# UniRF-Rev01.net
KiCad netlist of a schematic drawn in EAGLE
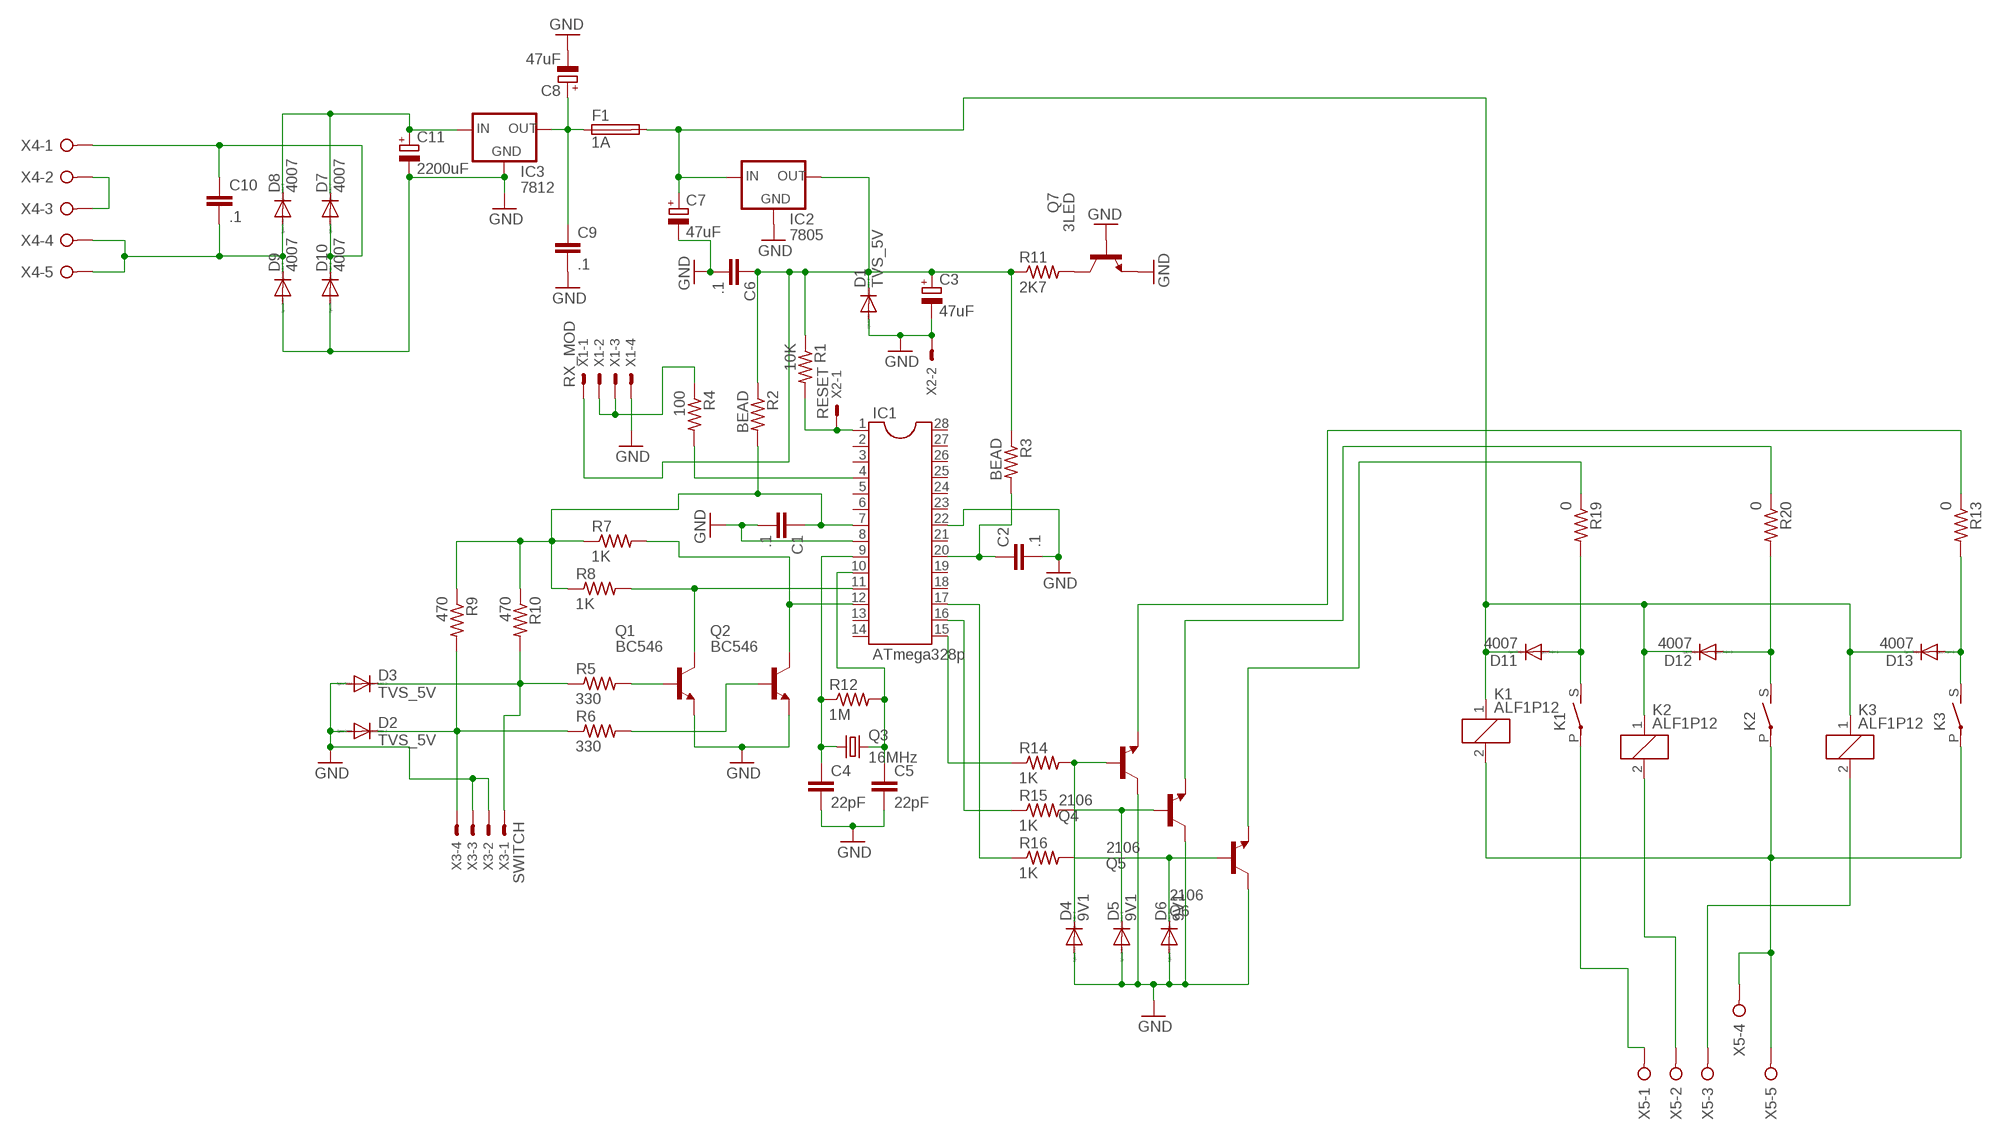
[diagram p0: schematic, sheet 1]

(export (version "E")
  (design (tool "Eeschema 10.0.6"))
  (components
    (comp (ref "C1")
      (value ".1")
      (footprint "eagle-import:C1210K")
      (libsource (lib "eagle-import") (part "C-EUC1210K"))
    )
    (comp (ref "C2")
      (value ".1")
      (footprint "eagle-import:C1210K")
      (libsource (lib "eagle-import") (part "C-EUC1210K"))
    )
    (comp (ref "C3")
      (value "47uF")
      (footprint "eagle-import:E5-8,5")
      (libsource (lib "eagle-import") (part "CPOL-EUE5-8.5"))
    )
    (comp (ref "C4")
      (value "22pF")
      (footprint "eagle-import:C1210K")
      (libsource (lib "eagle-import") (part "C-EUC1210K"))
    )
    (comp (ref "C5")
      (value "22pF")
      (footprint "eagle-import:C1210K")
      (libsource (lib "eagle-import") (part "C-EUC1210K"))
    )
    (comp (ref "C6")
      (value ".1")
      (footprint "eagle-import:C1210K")
      (libsource (lib "eagle-import") (part "C-EUC1210K"))
    )
    (comp (ref "C7")
      (value "47uF")
      (footprint "eagle-import:E5-8,5")
      (libsource (lib "eagle-import") (part "CPOL-EUE5-8.5"))
    )
    (comp (ref "C8")
      (value "47uF")
      (footprint "eagle-import:E5-8,5")
      (libsource (lib "eagle-import") (part "CPOL-EUE5-8.5"))
    )
    (comp (ref "C9")
      (value ".1")
      (footprint "eagle-import:C1210K")
      (libsource (lib "eagle-import") (part "C-EUC1210K"))
    )
    (comp (ref "C10")
      (value ".1")
      (footprint "eagle-import:C075-042X103")
      (libsource (lib "eagle-import") (part "C-EU075-042X103"))
    )
    (comp (ref "C11")
      (value "2200uF")
      (footprint "eagle-import:E7,5-18")
      (libsource (lib "eagle-import") (part "CPOL-EUE7.5-18"))
    )
    (comp (ref "D1")
      (value "TVS_5V")
      (footprint "eagle-import:DO35-10")
      (libsource (lib "eagle-import") (part "1N4148DO35-10"))
    )
    (comp (ref "D2")
      (value "TVS_5V")
      (footprint "eagle-import:DO35-10")
      (libsource (lib "eagle-import") (part "1N4148DO35-10"))
    )
    (comp (ref "D3")
      (value "TVS_5V")
      (footprint "eagle-import:DO35-10")
      (libsource (lib "eagle-import") (part "1N4148DO35-10"))
    )
    (comp (ref "D4")
      (value "9V1")
      (footprint "eagle-import:DO35-7")
      (libsource (lib "eagle-import") (part "1N4148DO35-7"))
    )
    (comp (ref "D5")
      (value "9V1")
      (footprint "eagle-import:DO35-7")
      (libsource (lib "eagle-import") (part "1N4148DO35-7"))
    )
    (comp (ref "D6")
      (value "9V1")
      (footprint "eagle-import:DO35-7")
      (libsource (lib "eagle-import") (part "1N4148DO35-7"))
    )
    (comp (ref "D7")
      (value "4007")
      (footprint "eagle-import:DO204-10")
      (libsource (lib "eagle-import") (part "1N5059"))
    )
    (comp (ref "D8")
      (value "4007")
      (footprint "eagle-import:DO204-10")
      (libsource (lib "eagle-import") (part "1N5059"))
    )
    (comp (ref "D9")
      (value "4007")
      (footprint "eagle-import:DO204-10")
      (libsource (lib "eagle-import") (part "1N5059"))
    )
    (comp (ref "D10")
      (value "4007")
      (footprint "eagle-import:DO204-10")
      (libsource (lib "eagle-import") (part "1N5059"))
    )
    (comp (ref "D11")
      (value "4007")
      (footprint "eagle-import:DO35-10")
      (libsource (lib "eagle-import") (part "1N4148DO35-10"))
    )
    (comp (ref "D12")
      (value "4007")
      (footprint "eagle-import:DO35-10")
      (libsource (lib "eagle-import") (part "1N4148DO35-10"))
    )
    (comp (ref "D13")
      (value "4007")
      (footprint "eagle-import:DO35-10")
      (libsource (lib "eagle-import") (part "1N4148DO35-10"))
    )
    (comp (ref "F1")
      (value "1A")
      (footprint "eagle-import:19560")
      (fields (field (name "MPN") "56000001009"))
      (libsource (lib "eagle-import") (part "19560"))
    )
    (comp (ref "IC1")
      (value "ATmega328p")
      (footprint "eagle-import:DIL28-3")
      (libsource (lib "eagle-import") (part "DIL28-3"))
    )
    (comp (ref "IC2")
      (value "7805")
      (footprint "eagle-import:78XXS")
      (libsource (lib "eagle-import") (part "78XXS"))
    )
    (comp (ref "IC3")
      (value "7812")
      (footprint "eagle-import:78XXS")
      (libsource (lib "eagle-import") (part "78XXS"))
    )
    (comp (ref "K1")
      (value "ALF1P12")
      (footprint "eagle-import:G2RA")
      (libsource (lib "eagle-import") (part "G2RA"))
    )
    (comp (ref "K2")
      (value "ALF1P12")
      (footprint "eagle-import:G2RA")
      (libsource (lib "eagle-import") (part "G2RA"))
    )
    (comp (ref "K3")
      (value "ALF1P12")
      (footprint "eagle-import:G2RA")
      (libsource (lib "eagle-import") (part "G2RA"))
    )
    (comp (ref "Q1")
      (value "BC546")
      (footprint "eagle-import:TO92-EBC")
      (libsource (lib "eagle-import") (part "BC546A"))
    )
    (comp (ref "Q2")
      (value "BC546")
      (footprint "eagle-import:TO92-EBC")
      (libsource (lib "eagle-import") (part "BC546A"))
    )
    (comp (ref "Q3")
      (value "16MHz")
      (footprint "eagle-import:HC49_S")
      (libsource (lib "eagle-import") (part "CRYSTALHC49S"))
    )
    (comp (ref "Q4")
      (value "2106")
      (footprint "eagle-import:TO92-EBC")
      (libsource (lib "eagle-import") (part "BC546A"))
    )
    (comp (ref "Q5")
      (value "2106")
      (footprint "eagle-import:TO92-EBC")
      (libsource (lib "eagle-import") (part "BC546A"))
    )
    (comp (ref "Q6")
      (value "2106")
      (footprint "eagle-import:TO92-EBC")
      (libsource (lib "eagle-import") (part "BC546A"))
    )
    (comp (ref "Q7")
      (value "3LED")
      (footprint "eagle-import:TO92-EBC")
      (libsource (lib "eagle-import") (part "BC546A"))
    )
    (comp (ref "R1")
      (value "10K")
      (footprint "eagle-import:0309_10")
      (libsource (lib "eagle-import") (part "R-US_0309/10"))
    )
    (comp (ref "R2")
      (value "BEAD")
      (footprint "eagle-import:0309_10")
      (libsource (lib "eagle-import") (part "R-US_0309/10"))
    )
    (comp (ref "R3")
      (value "BEAD")
      (footprint "eagle-import:0309_12")
      (libsource (lib "eagle-import") (part "R-US_0309/12"))
    )
    (comp (ref "R4")
      (value "100")
      (footprint "eagle-import:0309_10")
      (libsource (lib "eagle-import") (part "R-US_0309/10"))
    )
    (comp (ref "R5")
      (value "330")
      (footprint "eagle-import:0309_10")
      (libsource (lib "eagle-import") (part "R-US_0309/10"))
    )
    (comp (ref "R6")
      (value "330")
      (footprint "eagle-import:0309_10")
      (libsource (lib "eagle-import") (part "R-US_0309/10"))
    )
    (comp (ref "R7")
      (value "1K")
      (footprint "eagle-import:0309_10")
      (libsource (lib "eagle-import") (part "R-US_0309/10"))
    )
    (comp (ref "R8")
      (value "1K")
      (footprint "eagle-import:0309_10")
      (libsource (lib "eagle-import") (part "R-US_0309/10"))
    )
    (comp (ref "R9")
      (value "470")
      (footprint "eagle-import:0309_10")
      (libsource (lib "eagle-import") (part "R-US_0309/10"))
    )
    (comp (ref "R10")
      (value "470")
      (footprint "eagle-import:0309_10")
      (libsource (lib "eagle-import") (part "R-US_0309/10"))
    )
    (comp (ref "R11")
      (value "2K7")
      (footprint "eagle-import:0309_10")
      (libsource (lib "eagle-import") (part "R-US_0309/10"))
    )
    (comp (ref "R12")
      (value "1M")
      (footprint "eagle-import:0309V")
      (libsource (lib "eagle-import") (part "R-US_0309/V"))
    )
    (comp (ref "R13")
      (value "0")
      (footprint "eagle-import:0207_12")
      (libsource (lib "eagle-import") (part "R-US_0207/12"))
    )
    (comp (ref "R14")
      (value "1K")
      (footprint "eagle-import:R1210")
      (libsource (lib "eagle-import") (part "R-US_R1210"))
    )
    (comp (ref "R15")
      (value "1K")
      (footprint "eagle-import:R1210")
      (libsource (lib "eagle-import") (part "R-US_R1210"))
    )
    (comp (ref "R16")
      (value "1K")
      (footprint "eagle-import:R1210")
      (libsource (lib "eagle-import") (part "R-US_R1210"))
    )
    (comp (ref "R19")
      (value "0")
      (footprint "eagle-import:0207_12")
      (libsource (lib "eagle-import") (part "R-US_0207/12"))
    )
    (comp (ref "R20")
      (value "0")
      (footprint "eagle-import:0207_12")
      (libsource (lib "eagle-import") (part "R-US_0207/12"))
    )
    (comp (ref "X1")
      (value "RX_MOD")
      (footprint "eagle-import:22-23-2041")
      (fields (field (name "MF") "MOLEX") (field (name "MPN") "22-23-2041"))
      (libsource (lib "eagle-import") (part "22-23-2041"))
    )
    (comp (ref "X2")
      (value "RESET")
      (footprint "eagle-import:22-23-2021")
      (fields (field (name "MF") "MOLEX") (field (name "MPN") "22-23-2021"))
      (libsource (lib "eagle-import") (part "22-23-2021"))
    )
    (comp (ref "X3")
      (value "SWITCH")
      (footprint "eagle-import:22-23-2041")
      (fields (field (name "MF") "MOLEX") (field (name "MPN") "22-23-2041"))
      (libsource (lib "eagle-import") (part "22-23-2041"))
    )
    (comp (ref "X4")
      (value "W237-05P")
      (footprint "eagle-import:W237-5P")
      (libsource (lib "eagle-import") (part "W237-05P"))
    )
    (comp (ref "X5")
      (value "W237-05P")
      (footprint "eagle-import:W237-5P")
      (libsource (lib "eagle-import") (part "W237-05P"))
    )
  )
  (nets
    (net (code "1") (name "GND") (class "Default")
      (node (ref "C1") (pin "2") (pinfunction "2_2") (pintype "passive"))
      (node (ref "C11") (pin "-") (pinfunction "-_-") (pintype "passive"))
      (node (ref "C2") (pin "2") (pinfunction "2_2") (pintype "passive"))
      (node (ref "C3") (pin "-") (pinfunction "-_-") (pintype "passive"))
      (node (ref "C4") (pin "2") (pinfunction "2_2") (pintype "passive"))
      (node (ref "C5") (pin "2") (pinfunction "2_2") (pintype "passive"))
      (node (ref "C6") (pin "2") (pinfunction "2_2") (pintype "passive"))
      (node (ref "C7") (pin "-") (pinfunction "-_-") (pintype "passive"))
      (node (ref "C8") (pin "-") (pinfunction "-_-") (pintype "passive"))
      (node (ref "C9") (pin "2") (pinfunction "2_2") (pintype "passive"))
      (node (ref "D1") (pin "A") (pinfunction "A_A") (pintype "passive"))
      (node (ref "D10") (pin "A") (pinfunction "A_A") (pintype "passive"))
      (node (ref "D2") (pin "A") (pinfunction "A_A") (pintype "passive"))
      (node (ref "D3") (pin "A") (pinfunction "A_A") (pintype "passive"))
      (node (ref "D4") (pin "A") (pinfunction "A_A") (pintype "passive"))
      (node (ref "D5") (pin "A") (pinfunction "A_A") (pintype "passive"))
      (node (ref "D6") (pin "A") (pinfunction "A_A") (pintype "passive"))
      (node (ref "D9") (pin "A") (pinfunction "A_A") (pintype "passive"))
      (node (ref "IC1") (pin "22") (pinfunction "22_22") (pintype "passive"))
      (node (ref "IC1") (pin "8") (pinfunction "8_8") (pintype "passive"))
      (node (ref "IC2") (pin "GND") (pinfunction "GND_GND") (pintype "input"))
      (node (ref "IC3") (pin "GND") (pinfunction "GND_GND") (pintype "input"))
      (node (ref "Q1") (pin "E") (pinfunction "E_E") (pintype "passive"))
      (node (ref "Q2") (pin "E") (pinfunction "E_E") (pintype "passive"))
      (node (ref "Q4") (pin "C") (pinfunction "C_C") (pintype "passive"))
      (node (ref "Q5") (pin "C") (pinfunction "C_C") (pintype "passive"))
      (node (ref "Q6") (pin "C") (pinfunction "C_C") (pintype "passive"))
      (node (ref "Q7") (pin "B") (pinfunction "B_B") (pintype "passive"))
      (node (ref "Q7") (pin "E") (pinfunction "E_E") (pintype "passive"))
      (node (ref "X1") (pin "4") (pinfunction "S_4") (pintype "passive"))
      (node (ref "X2") (pin "2") (pinfunction "S_2") (pintype "passive"))
      (node (ref "X3") (pin "2") (pinfunction "S_2") (pintype "passive"))
      (node (ref "X3") (pin "3") (pinfunction "S_3") (pintype "passive"))
    )
    (net (code "2") (name "Net-(C1-Pad1)") (class "Default")
      (node (ref "C1") (pin "1") (pinfunction "1_1") (pintype "passive"))
      (node (ref "IC1") (pin "7") (pinfunction "7_7") (pintype "passive"))
      (node (ref "R10") (pin "1") (pinfunction "1_1") (pintype "passive"))
      (node (ref "R2") (pin "2") (pinfunction "2_2") (pintype "passive"))
      (node (ref "R7") (pin "1") (pinfunction "1_1") (pintype "passive"))
      (node (ref "R8") (pin "1") (pinfunction "1_1") (pintype "passive"))
      (node (ref "R9") (pin "1") (pinfunction "1_1") (pintype "passive"))
    )
    (net (code "3") (name "Net-(C2-Pad1)") (class "Default")
      (node (ref "C2") (pin "1") (pinfunction "1_1") (pintype "passive"))
      (node (ref "IC1") (pin "20") (pinfunction "20_20") (pintype "passive"))
      (node (ref "R3") (pin "2") (pinfunction "2_2") (pintype "passive"))
    )
    (net (code "4") (name "Net-(C4-Pad1)") (class "Default")
      (node (ref "C4") (pin "1") (pinfunction "1_1") (pintype "passive"))
      (node (ref "IC1") (pin "9") (pinfunction "9_9") (pintype "passive"))
      (node (ref "Q3") (pin "1") (pinfunction "1_1") (pintype "passive"))
      (node (ref "R12") (pin "1") (pinfunction "1_1") (pintype "passive"))
    )
    (net (code "5") (name "Net-(C5-Pad1)") (class "Default")
      (node (ref "C5") (pin "1") (pinfunction "1_1") (pintype "passive"))
      (node (ref "IC1") (pin "10") (pinfunction "10_10") (pintype "passive"))
      (node (ref "Q3") (pin "2") (pinfunction "2_2") (pintype "passive"))
      (node (ref "R12") (pin "2") (pinfunction "2_2") (pintype "passive"))
    )
    (net (code "6") (name "Net-(C7-Pad+)") (class "Default")
      (node (ref "C7") (pin "+") (pinfunction "+_+") (pintype "passive"))
      (node (ref "D11") (pin "C") (pinfunction "C_C") (pintype "passive"))
      (node (ref "D12") (pin "C") (pinfunction "C_C") (pintype "passive"))
      (node (ref "D13") (pin "C") (pinfunction "C_C") (pintype "passive"))
      (node (ref "F1") (pin "2") (pinfunction "2_2") (pintype "passive"))
      (node (ref "IC2") (pin "IN") (pinfunction "IN_IN") (pintype "input"))
      (node (ref "K1") (pin "1") (pinfunction "1_1") (pintype "passive"))
      (node (ref "K2") (pin "1") (pinfunction "1_1") (pintype "passive"))
      (node (ref "K3") (pin "1") (pinfunction "1_1") (pintype "passive"))
    )
    (net (code "7") (name "Net-(C8-Pad+)") (class "Default")
      (node (ref "C8") (pin "+") (pinfunction "+_+") (pintype "passive"))
      (node (ref "C9") (pin "1") (pinfunction "1_1") (pintype "passive"))
      (node (ref "F1") (pin "1") (pinfunction "1_1") (pintype "passive"))
      (node (ref "IC3") (pin "OUT") (pinfunction "OUT_OUT") (pintype "passive"))
    )
    (net (code "8") (name "Net-(C11-Pad+)") (class "Default")
      (node (ref "C11") (pin "+") (pinfunction "+_+") (pintype "passive"))
      (node (ref "D7") (pin "C") (pinfunction "C_C") (pintype "passive"))
      (node (ref "D8") (pin "C") (pinfunction "C_C") (pintype "passive"))
      (node (ref "IC3") (pin "IN") (pinfunction "IN_IN") (pintype "input"))
    )
    (net (code "9") (name "Net-(D4-PadC)") (class "Default")
      (node (ref "D4") (pin "C") (pinfunction "C_C") (pintype "passive"))
      (node (ref "Q4") (pin "B") (pinfunction "B_B") (pintype "passive"))
      (node (ref "R14") (pin "2") (pinfunction "2_2") (pintype "passive"))
    )
    (net (code "10") (name "Net-(D5-PadC)") (class "Default")
      (node (ref "D5") (pin "C") (pinfunction "C_C") (pintype "passive"))
      (node (ref "Q5") (pin "B") (pinfunction "B_B") (pintype "passive"))
      (node (ref "R15") (pin "2") (pinfunction "2_2") (pintype "passive"))
    )
    (net (code "11") (name "Net-(D6-PadC)") (class "Default")
      (node (ref "D6") (pin "C") (pinfunction "C_C") (pintype "passive"))
      (node (ref "Q6") (pin "B") (pinfunction "B_B") (pintype "passive"))
      (node (ref "R16") (pin "2") (pinfunction "2_2") (pintype "passive"))
    )
    (net (code "12") (name "Net-(D11-PadA)") (class "Default")
      (node (ref "D11") (pin "A") (pinfunction "A_A") (pintype "passive"))
      (node (ref "K1") (pin "S") (pinfunction "S_S") (pintype "passive"))
      (node (ref "R19") (pin "2") (pinfunction "2_2") (pintype "passive"))
    )
    (net (code "13") (name "Net-(D12-PadA)") (class "Default")
      (node (ref "D12") (pin "A") (pinfunction "A_A") (pintype "passive"))
      (node (ref "K2") (pin "S") (pinfunction "S_S") (pintype "passive"))
      (node (ref "R20") (pin "2") (pinfunction "2_2") (pintype "passive"))
    )
    (net (code "14") (name "Net-(D13-PadA)") (class "Default")
      (node (ref "D13") (pin "A") (pinfunction "A_A") (pintype "passive"))
      (node (ref "K3") (pin "S") (pinfunction "S_S") (pintype "passive"))
      (node (ref "R13") (pin "2") (pinfunction "2_2") (pintype "passive"))
    )
    (net (code "15") (name "Net-(IC1-Pad4)") (class "Default")
      (node (ref "IC1") (pin "4") (pinfunction "4_4") (pintype "passive"))
      (node (ref "R4") (pin "2") (pinfunction "2_2") (pintype "passive"))
    )
    (net (code "16") (name "Net-(IC1-Pad11)") (class "Default")
      (node (ref "IC1") (pin "11") (pinfunction "11_11") (pintype "passive"))
      (node (ref "Q1") (pin "C") (pinfunction "C_C") (pintype "passive"))
      (node (ref "R8") (pin "2") (pinfunction "2_2") (pintype "passive"))
    )
    (net (code "17") (name "Net-(IC1-Pad12)") (class "Default")
      (node (ref "IC1") (pin "12") (pinfunction "12_12") (pintype "passive"))
      (node (ref "Q2") (pin "C") (pinfunction "C_C") (pintype "passive"))
      (node (ref "R7") (pin "2") (pinfunction "2_2") (pintype "passive"))
    )
    (net (code "18") (name "Net-(IC1-Pad15)") (class "Default")
      (node (ref "IC1") (pin "15") (pinfunction "15_15") (pintype "passive"))
      (node (ref "R14") (pin "1") (pinfunction "1_1") (pintype "passive"))
    )
    (net (code "19") (name "Net-(IC1-Pad16)") (class "Default")
      (node (ref "IC1") (pin "16") (pinfunction "16_16") (pintype "passive"))
      (node (ref "R15") (pin "1") (pinfunction "1_1") (pintype "passive"))
    )
    (net (code "20") (name "Net-(IC1-Pad17)") (class "Default")
      (node (ref "IC1") (pin "17") (pinfunction "17_17") (pintype "passive"))
      (node (ref "R16") (pin "1") (pinfunction "1_1") (pintype "passive"))
    )
    (net (code "21") (name "Net-(Q1-PadB)") (class "Default")
      (node (ref "Q1") (pin "B") (pinfunction "B_B") (pintype "passive"))
      (node (ref "R5") (pin "2") (pinfunction "2_2") (pintype "passive"))
    )
    (net (code "22") (name "Net-(Q2-PadB)") (class "Default")
      (node (ref "Q2") (pin "B") (pinfunction "B_B") (pintype "passive"))
      (node (ref "R6") (pin "2") (pinfunction "2_2") (pintype "passive"))
    )
    (net (code "23") (name "Net-(Q4-PadE)") (class "Default")
      (node (ref "Q4") (pin "E") (pinfunction "E_E") (pintype "passive"))
      (node (ref "R13") (pin "1") (pinfunction "1_1") (pintype "passive"))
    )
    (net (code "24") (name "Net-(Q5-PadE)") (class "Default")
      (node (ref "Q5") (pin "E") (pinfunction "E_E") (pintype "passive"))
      (node (ref "R20") (pin "1") (pinfunction "1_1") (pintype "passive"))
    )
    (net (code "25") (name "Net-(Q6-PadE)") (class "Default")
      (node (ref "Q6") (pin "E") (pinfunction "E_E") (pintype "passive"))
      (node (ref "R19") (pin "1") (pinfunction "1_1") (pintype "passive"))
    )
    (net (code "26") (name "Net-(Q7-PadC)") (class "Default")
      (node (ref "Q7") (pin "C") (pinfunction "C_C") (pintype "passive"))
      (node (ref "R11") (pin "2") (pinfunction "2_2") (pintype "passive"))
    )
    (net (code "27") (name "Net-(X1A-S)") (class "Default")
      (node (ref "C3") (pin "+") (pinfunction "+_+") (pintype "passive"))
      (node (ref "C6") (pin "1") (pinfunction "1_1") (pintype "passive"))
      (node (ref "D1") (pin "C") (pinfunction "C_C") (pintype "passive"))
      (node (ref "IC2") (pin "OUT") (pinfunction "OUT_OUT") (pintype "passive"))
      (node (ref "R1") (pin "1") (pinfunction "1_1") (pintype "passive"))
      (node (ref "R11") (pin "1") (pinfunction "1_1") (pintype "passive"))
      (node (ref "R2") (pin "1") (pinfunction "1_1") (pintype "passive"))
      (node (ref "R3") (pin "1") (pinfunction "1_1") (pintype "passive"))
      (node (ref "X1") (pin "1") (pinfunction "S_1") (pintype "passive"))
    )
    (net (code "28") (name "Net-(X1B-S)") (class "Default")
      (node (ref "R4") (pin "1") (pinfunction "1_1") (pintype "passive"))
      (node (ref "X1") (pin "2") (pinfunction "S_2") (pintype "passive"))
      (node (ref "X1") (pin "3") (pinfunction "S_3") (pintype "passive"))
    )
    (net (code "29") (name "Net-(X2A-S)") (class "Default")
      (node (ref "IC1") (pin "1") (pinfunction "1_1") (pintype "passive"))
      (node (ref "R1") (pin "2") (pinfunction "2_2") (pintype "passive"))
      (node (ref "X2") (pin "1") (pinfunction "S_1") (pintype "passive"))
    )
    (net (code "30") (name "Net-(X3A-S)") (class "Default")
      (node (ref "D3") (pin "C") (pinfunction "C_C") (pintype "passive"))
      (node (ref "R10") (pin "2") (pinfunction "2_2") (pintype "passive"))
      (node (ref "R5") (pin "1") (pinfunction "1_1") (pintype "passive"))
      (node (ref "X3") (pin "1") (pinfunction "S_1") (pintype "passive"))
    )
    (net (code "31") (name "Net-(X3D-S)") (class "Default")
      (node (ref "D2") (pin "C") (pinfunction "C_C") (pintype "passive"))
      (node (ref "R6") (pin "1") (pinfunction "1_1") (pintype "passive"))
      (node (ref "R9") (pin "2") (pinfunction "2_2") (pintype "passive"))
      (node (ref "X3") (pin "4") (pinfunction "S_4") (pintype "passive"))
    )
    (net (code "32") (name "Net-(X4A-KL)") (class "Default")
      (node (ref "C10") (pin "1") (pinfunction "1_1") (pintype "passive"))
      (node (ref "D10") (pin "C") (pinfunction "C_C") (pintype "passive"))
      (node (ref "D7") (pin "A") (pinfunction "A_A") (pintype "passive"))
      (node (ref "X4") (pin "1") (pinfunction "KL_1") (pintype "passive"))
    )
    (net (code "33") (name "Net-(X4B-KL)") (class "Default")
      (node (ref "X4") (pin "2") (pinfunction "KL_2") (pintype "passive"))
      (node (ref "X4") (pin "3") (pinfunction "KL_3") (pintype "passive"))
    )
    (net (code "34") (name "Net-(X4D-KL)") (class "Default")
      (node (ref "C10") (pin "2") (pinfunction "2_2") (pintype "passive"))
      (node (ref "D8") (pin "A") (pinfunction "A_A") (pintype "passive"))
      (node (ref "D9") (pin "C") (pinfunction "C_C") (pintype "passive"))
      (node (ref "X4") (pin "4") (pinfunction "KL_4") (pintype "passive"))
      (node (ref "X4") (pin "5") (pinfunction "KL_5") (pintype "passive"))
    )
    (net (code "35") (name "Net-(X5A-KL)") (class "Default")
      (node (ref "K1") (pin "P") (pinfunction "P_P") (pintype "passive"))
      (node (ref "X5") (pin "1") (pinfunction "KL_1") (pintype "passive"))
    )
    (net (code "36") (name "Net-(X5B-KL)") (class "Default")
      (node (ref "K2") (pin "2") (pinfunction "2_2") (pintype "passive"))
      (node (ref "X5") (pin "2") (pinfunction "KL_2") (pintype "passive"))
    )
    (net (code "37") (name "Net-(X5C-KL)") (class "Default")
      (node (ref "K3") (pin "2") (pinfunction "2_2") (pintype "passive"))
      (node (ref "X5") (pin "3") (pinfunction "KL_3") (pintype "passive"))
    )
    (net (code "38") (name "Net-(X5D-KL)") (class "Default")
      (node (ref "K1") (pin "2") (pinfunction "2_2") (pintype "passive"))
      (node (ref "K2") (pin "P") (pinfunction "P_P") (pintype "passive"))
      (node (ref "K3") (pin "P") (pinfunction "P_P") (pintype "passive"))
      (node (ref "X5") (pin "4") (pinfunction "KL_4") (pintype "passive"))
      (node (ref "X5") (pin "5") (pinfunction "KL_5") (pintype "passive"))
    )
    (net (code "39") (name "unconnected-(IC1-Pad2)") (class "Default")
      (node (ref "IC1") (pin "2") (pinfunction "2_2") (pintype "passive"))
    )
    (net (code "40") (name "unconnected-(IC1-Pad3)") (class "Default")
      (node (ref "IC1") (pin "3") (pinfunction "3_3") (pintype "passive"))
    )
    (net (code "41") (name "unconnected-(IC1-Pad5)") (class "Default")
      (node (ref "IC1") (pin "5") (pinfunction "5_5") (pintype "passive"))
    )
    (net (code "42") (name "unconnected-(IC1-Pad6)") (class "Default")
      (node (ref "IC1") (pin "6") (pinfunction "6_6") (pintype "passive"))
    )
    (net (code "43") (name "unconnected-(IC1-Pad13)") (class "Default")
      (node (ref "IC1") (pin "13") (pinfunction "13_13") (pintype "passive"))
    )
    (net (code "44") (name "unconnected-(IC1-Pad14)") (class "Default")
      (node (ref "IC1") (pin "14") (pinfunction "14_14") (pintype "passive"))
    )
    (net (code "45") (name "unconnected-(IC1-Pad18)") (class "Default")
      (node (ref "IC1") (pin "18") (pinfunction "18_18") (pintype "passive"))
    )
    (net (code "46") (name "unconnected-(IC1-Pad19)") (class "Default")
      (node (ref "IC1") (pin "19") (pinfunction "19_19") (pintype "passive"))
    )
    (net (code "47") (name "unconnected-(IC1-Pad21)") (class "Default")
      (node (ref "IC1") (pin "21") (pinfunction "21_21") (pintype "passive"))
    )
    (net (code "48") (name "unconnected-(IC1-Pad23)") (class "Default")
      (node (ref "IC1") (pin "23") (pinfunction "23_23") (pintype "passive"))
    )
    (net (code "49") (name "unconnected-(IC1-Pad24)") (class "Default")
      (node (ref "IC1") (pin "24") (pinfunction "24_24") (pintype "passive"))
    )
    (net (code "50") (name "unconnected-(IC1-Pad25)") (class "Default")
      (node (ref "IC1") (pin "25") (pinfunction "25_25") (pintype "passive"))
    )
    (net (code "51") (name "unconnected-(IC1-Pad26)") (class "Default")
      (node (ref "IC1") (pin "26") (pinfunction "26_26") (pintype "passive"))
    )
    (net (code "52") (name "unconnected-(IC1-Pad27)") (class "Default")
      (node (ref "IC1") (pin "27") (pinfunction "27_27") (pintype "passive"))
    )
    (net (code "53") (name "unconnected-(IC1-Pad28)") (class "Default")
      (node (ref "IC1") (pin "28") (pinfunction "28_28") (pintype "passive"))
    )
  )
)
